# B_reg.net
KiCad netlist of a schematic drawn in EAGLE
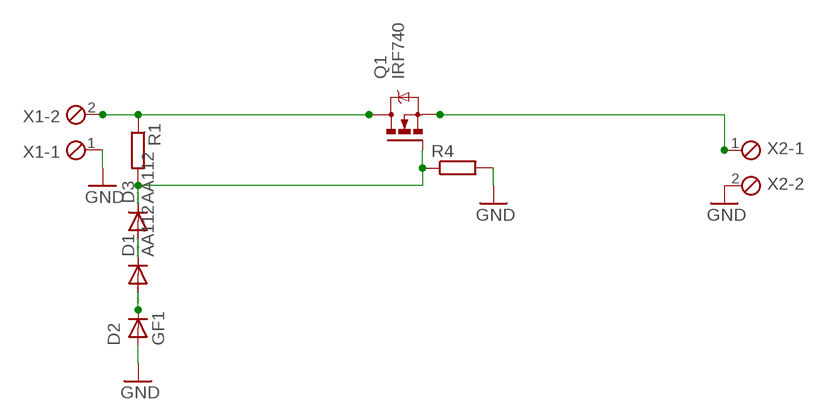
[diagram p0: schematic, sheet 1]

(export (version "E")
  (design (tool "Eeschema 10.0.6"))
  (components
    (comp (ref "D1")
      (value "AA112")
      (footprint "eagle-import:DO07")
      (libsource (lib "eagle-import") (part "AA112"))
    )
    (comp (ref "D2")
      (value "GF1")
      (footprint "eagle-import:SMA-DO214AC")
      (libsource (lib "eagle-import") (part "GF1"))
    )
    (comp (ref "D3")
      (value "AA112")
      (footprint "eagle-import:DO07")
      (libsource (lib "eagle-import") (part "AA112"))
    )
    (comp (ref "Q1")
      (value "IRF740")
      (footprint "eagle-import:TO220BV")
      (libsource (lib "eagle-import") (part "IRF740"))
    )
    (comp (ref "R1")
      (value "R-EU_R0805")
      (footprint "eagle-import:R0805")
      (libsource (lib "eagle-import") (part "R-EU_R0805"))
    )
    (comp (ref "R4")
      (value "R-EU_R0805")
      (footprint "eagle-import:R0805")
      (libsource (lib "eagle-import") (part "R-EU_R0805"))
    )
    (comp (ref "X1")
      (value "MPT2")
      (footprint "eagle-import:2POL254")
      (libsource (lib "eagle-import") (part "MPT2"))
    )
    (comp (ref "X2")
      (value "MPT2")
      (footprint "eagle-import:2POL254")
      (libsource (lib "eagle-import") (part "MPT2"))
    )
  )
  (nets
    (net (code "1") (name "GND") (class "Default")
      (node (ref "D2") (pin "A") (pinfunction "A_A") (pintype "passive"))
      (node (ref "R4") (pin "2") (pinfunction "2_2") (pintype "passive"))
      (node (ref "X1") (pin "1") (pinfunction "1_1") (pintype "passive"))
      (node (ref "X2") (pin "2") (pinfunction "1_2") (pintype "passive"))
    )
    (net (code "2") (name "Net-(D1-PadC)") (class "Default")
      (node (ref "D1") (pin "C") (pinfunction "C_C") (pintype "passive"))
      (node (ref "D3") (pin "A") (pinfunction "A_A") (pintype "passive"))
    )
    (net (code "3") (name "Net-(D2-C)") (class "Default")
      (node (ref "D1") (pin "A") (pinfunction "A_A") (pintype "passive"))
      (node (ref "D2") (pin "K") (pinfunction "C_K") (pintype "passive"))
    )
    (net (code "4") (name "Net-(D3-PadC)") (class "Default")
      (node (ref "D3") (pin "C") (pinfunction "C_C") (pintype "passive"))
      (node (ref "Q1") (pin "G") (pinfunction "G_G") (pintype "passive"))
      (node (ref "R1") (pin "2") (pinfunction "2_2") (pintype "passive"))
      (node (ref "R4") (pin "1") (pinfunction "1_1") (pintype "passive"))
    )
    (net (code "5") (name "Net-(Q1-PadS)") (class "Default")
      (node (ref "Q1") (pin "S") (pinfunction "S_S") (pintype "passive"))
      (node (ref "X2") (pin "1") (pinfunction "1_1") (pintype "passive"))
    )
    (net (code "6") (name "Net-(X1B-1)") (class "Default")
      (node (ref "Q1") (pin "D") (pinfunction "D_D") (pintype "passive"))
      (node (ref "R1") (pin "1") (pinfunction "1_1") (pintype "passive"))
      (node (ref "X1") (pin "2") (pinfunction "1_2") (pintype "passive"))
    )
  )
)
